# E77N.net
KiCad netlist of a schematic drawn in Altium Designer
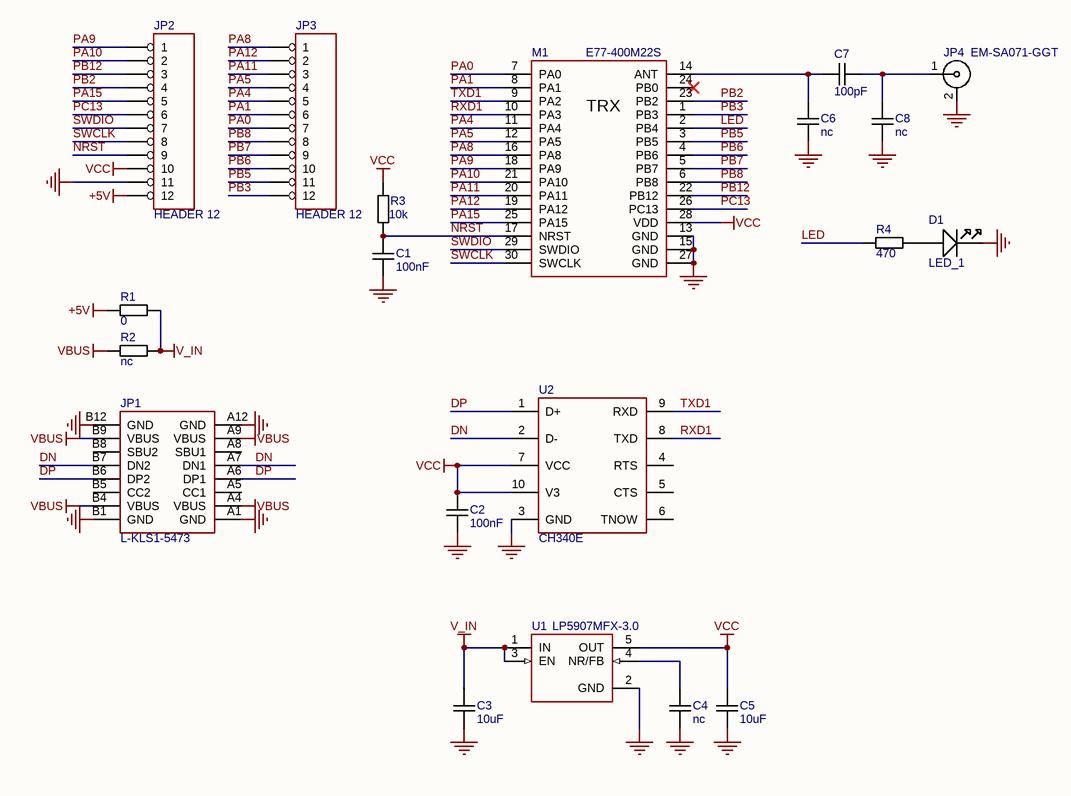
[diagram p0: E77N.SchDoc]

(export (version "E")
  (design (tool "Eeschema 10.0.6"))
  (components
    (comp (ref "C1")
      (value "100nF")
      (footprint "C-0603")
      (fields (field (name "VOLTAGE") "50V"))
      (libsource (lib "Passive") (part "CAPN"))
    )
    (comp (ref "C2")
      (value "100nF")
      (footprint "C-0603")
      (fields (field (name "VOLTAGE") "50V"))
      (libsource (lib "Passive") (part "CAPN"))
    )
    (comp (ref "C3")
      (value "10uF")
      (footprint "C-0805")
      (fields (field (name "VOLTAGE") "50V"))
      (libsource (lib "Passive") (part "CAPN"))
    )
    (comp (ref "C4")
      (value "nc")
      (footprint "C-0603")
      (fields (field (name "VOLTAGE") "50V"))
      (libsource (lib "Passive") (part "CAPN"))
    )
    (comp (ref "C5")
      (value "10uF")
      (footprint "C-0805")
      (fields (field (name "VOLTAGE") "50V"))
      (libsource (lib "Passive") (part "CAPN"))
    )
    (comp (ref "C6")
      (value "nc")
      (footprint "C-0603")
      (fields (field (name "VOLTAGE") "50V"))
      (libsource (lib "Passive") (part "CAPN"))
    )
    (comp (ref "C7")
      (value "100pF")
      (footprint "C-0603")
      (fields (field (name "VOLTAGE") "50V"))
      (libsource (lib "Passive") (part "CAPN"))
    )
    (comp (ref "C8")
      (value "nc")
      (footprint "C-0603")
      (fields (field (name "VOLTAGE") "50V"))
      (libsource (lib "Passive") (part "CAPN"))
    )
    (comp (ref "D1") (value "LED_1") (footprint "LED_0805") (libsource (lib "Diodes") (part "LED_1")))
    (comp (ref "JP1")
      (value "L-KLS1-5473")
      (footprint "USB_C_SMD_SLOT")
      (libsource (lib "Connectors") (part "L-KLS1-5473"))
    )
    (comp (ref "JP2")
      (value "HEADER 12")
      (footprint "PLS1-12")
      (libsource (lib "Connectors") (part "HEADER 12"))
    )
    (comp (ref "JP3")
      (value "HEADER 12")
      (footprint "PLS1-12")
      (libsource (lib "Connectors") (part "HEADER 12"))
    )
    (comp (ref "JP4")
      (value "EM-SA071-GGT")
      (footprint "SMA_F_EDGE")
      (description "SMA Female R/A PCB Mount")
      (libsource (lib "Connectors") (part "SMA"))
    )
    (comp (ref "M1")
      (value "E77-400M22S")
      (footprint "E77XX-M22")
      (libsource (lib "RFmodules") (part "E77-400M22S"))
    )
    (comp (ref "R1") (value "0") (footprint "R-0603") (libsource (lib "") (part "RES_1")))
    (comp (ref "R2") (value "nc") (footprint "R-0603") (libsource (lib "") (part "RES_1")))
    (comp (ref "R3") (value "10k") (footprint "R-0603") (libsource (lib "Passive") (part "RES")))
    (comp (ref "R4") (value "470") (footprint "R-0603") (libsource (lib "") (part "RES_2")))
    (comp (ref "U1")
      (value "LP5907MFX-3.0")
      (footprint "SOT-23-5")
      (description "250mA Low-Dropout Regulator")
      (libsource (lib "ICs") (part "LP5907"))
    )
    (comp (ref "U2") (value "CH340E") (footprint "MSOP-10") (libsource (lib "ICs") (part "CH340E")))
  )
  (nets
    (net (code "1") (name "+5V") (class "Default")
      (node (ref "JP2") (pin "12") (pinfunction "12_12") (pintype "passive"))
      (node (ref "R1") (pin "1") (pinfunction "1_1") (pintype "passive"))
    )
    (net (code "2") (name "/DN") (class "Default")
      (node (ref "JP1") (pin "A7") (pinfunction "DN1_A7") (pintype "passive"))
      (node (ref "JP1") (pin "B7") (pinfunction "DN2_B7") (pintype "passive"))
      (node (ref "U2") (pin "2") (pinfunction "D-_2") (pintype "passive"))
    )
    (net (code "3") (name "/DP") (class "Default")
      (node (ref "JP1") (pin "A6") (pinfunction "DP1_A6") (pintype "passive"))
      (node (ref "JP1") (pin "B6") (pinfunction "DP2_B6") (pintype "passive"))
      (node (ref "U2") (pin "1") (pinfunction "D+_1") (pintype "passive"))
    )
    (net (code "4") (name "/LED") (class "Default")
      (node (ref "M1") (pin "2") (pinfunction "PB4_2") (pintype "passive"))
      (node (ref "R4") (pin "2") (pinfunction "2_2") (pintype "passive"))
    )
    (net (code "5") (name "/NRST") (class "Default")
      (node (ref "C1") (pin "2") (pinfunction "2_2") (pintype "passive"))
      (node (ref "JP2") (pin "9") (pinfunction "9_9") (pintype "passive"))
      (node (ref "M1") (pin "17") (pinfunction "NRST_17") (pintype "passive"))
      (node (ref "R3") (pin "1") (pinfunction "1_1") (pintype "passive"))
    )
    (net (code "6") (name "/PA0") (class "Default")
      (node (ref "JP3") (pin "7") (pinfunction "7_7") (pintype "passive"))
      (node (ref "M1") (pin "7") (pinfunction "PA0_7") (pintype "passive"))
    )
    (net (code "7") (name "/PA1") (class "Default")
      (node (ref "JP3") (pin "6") (pinfunction "6_6") (pintype "passive"))
      (node (ref "M1") (pin "8") (pinfunction "PA1_8") (pintype "passive"))
    )
    (net (code "8") (name "/PA4") (class "Default")
      (node (ref "JP3") (pin "5") (pinfunction "5_5") (pintype "passive"))
      (node (ref "M1") (pin "11") (pinfunction "PA4_11") (pintype "passive"))
    )
    (net (code "9") (name "/PA5") (class "Default")
      (node (ref "JP3") (pin "4") (pinfunction "4_4") (pintype "passive"))
      (node (ref "M1") (pin "12") (pinfunction "PA5_12") (pintype "passive"))
    )
    (net (code "10") (name "/PA8") (class "Default")
      (node (ref "JP3") (pin "1") (pinfunction "1_1") (pintype "passive"))
      (node (ref "M1") (pin "16") (pinfunction "PA8_16") (pintype "passive"))
    )
    (net (code "11") (name "/PA9") (class "Default")
      (node (ref "JP2") (pin "1") (pinfunction "1_1") (pintype "passive"))
      (node (ref "M1") (pin "18") (pinfunction "PA9_18") (pintype "passive"))
    )
    (net (code "12") (name "/PA10") (class "Default")
      (node (ref "JP2") (pin "2") (pinfunction "2_2") (pintype "passive"))
      (node (ref "M1") (pin "21") (pinfunction "PA10_21") (pintype "passive"))
    )
    (net (code "13") (name "/PA11") (class "Default")
      (node (ref "JP3") (pin "3") (pinfunction "3_3") (pintype "passive"))
      (node (ref "M1") (pin "20") (pinfunction "PA11_20") (pintype "passive"))
    )
    (net (code "14") (name "/PA12") (class "Default")
      (node (ref "JP3") (pin "2") (pinfunction "2_2") (pintype "passive"))
      (node (ref "M1") (pin "19") (pinfunction "PA12_19") (pintype "passive"))
    )
    (net (code "15") (name "/PA15") (class "Default")
      (node (ref "JP2") (pin "5") (pinfunction "5_5") (pintype "passive"))
      (node (ref "M1") (pin "25") (pinfunction "PA15_25") (pintype "passive"))
    )
    (net (code "16") (name "/PB2") (class "Default")
      (node (ref "JP2") (pin "4") (pinfunction "4_4") (pintype "passive"))
      (node (ref "M1") (pin "23") (pinfunction "PB2_23") (pintype "passive"))
    )
    (net (code "17") (name "/PB3") (class "Default")
      (node (ref "JP3") (pin "12") (pinfunction "12_12") (pintype "passive"))
      (node (ref "M1") (pin "1") (pinfunction "PB3_1") (pintype "passive"))
    )
    (net (code "18") (name "/PB5") (class "Default")
      (node (ref "JP3") (pin "11") (pinfunction "11_11") (pintype "passive"))
      (node (ref "M1") (pin "3") (pinfunction "PB5_3") (pintype "passive"))
    )
    (net (code "19") (name "/PB6") (class "Default")
      (node (ref "JP3") (pin "10") (pinfunction "10_10") (pintype "passive"))
      (node (ref "M1") (pin "4") (pinfunction "PB6_4") (pintype "passive"))
    )
    (net (code "20") (name "/PB7") (class "Default")
      (node (ref "JP3") (pin "9") (pinfunction "9_9") (pintype "passive"))
      (node (ref "M1") (pin "5") (pinfunction "PB7_5") (pintype "passive"))
    )
    (net (code "21") (name "/PB8") (class "Default")
      (node (ref "JP3") (pin "8") (pinfunction "8_8") (pintype "passive"))
      (node (ref "M1") (pin "6") (pinfunction "PB8_6") (pintype "passive"))
    )
    (net (code "22") (name "/PB12") (class "Default")
      (node (ref "JP2") (pin "3") (pinfunction "3_3") (pintype "passive"))
      (node (ref "M1") (pin "22") (pinfunction "PB12_22") (pintype "passive"))
    )
    (net (code "23") (name "/PC13") (class "Default")
      (node (ref "JP2") (pin "6") (pinfunction "6_6") (pintype "passive"))
      (node (ref "M1") (pin "26") (pinfunction "PC13_26") (pintype "passive"))
    )
    (net (code "24") (name "/RXD1") (class "Default")
      (node (ref "M1") (pin "10") (pinfunction "PA3_10") (pintype "passive"))
      (node (ref "U2") (pin "8") (pinfunction "TXD_8") (pintype "passive"))
    )
    (net (code "25") (name "/SWCLK") (class "Default")
      (node (ref "JP2") (pin "8") (pinfunction "8_8") (pintype "passive"))
      (node (ref "M1") (pin "30") (pinfunction "SWCLK_30") (pintype "passive"))
    )
    (net (code "26") (name "/SWDIO") (class "Default")
      (node (ref "JP2") (pin "7") (pinfunction "7_7") (pintype "passive"))
      (node (ref "M1") (pin "29") (pinfunction "SWDIO_29") (pintype "passive"))
    )
    (net (code "27") (name "/TXD1") (class "Default")
      (node (ref "M1") (pin "9") (pinfunction "PA2_9") (pintype "passive"))
      (node (ref "U2") (pin "9") (pinfunction "RXD_9") (pintype "passive"))
    )
    (net (code "28") (name "GND") (class "Default")
      (node (ref "C1") (pin "1") (pinfunction "1_1") (pintype "passive"))
      (node (ref "C2") (pin "1") (pinfunction "1_1") (pintype "passive"))
      (node (ref "C3") (pin "2") (pinfunction "2_2") (pintype "passive"))
      (node (ref "C4") (pin "2") (pinfunction "2_2") (pintype "passive"))
      (node (ref "C5") (pin "2") (pinfunction "2_2") (pintype "passive"))
      (node (ref "C6") (pin "1") (pinfunction "1_1") (pintype "passive"))
      (node (ref "C8") (pin "1") (pinfunction "1_1") (pintype "passive"))
      (node (ref "D1") (pin "K") (pinfunction "CATHODE_K") (pintype "passive"))
      (node (ref "JP1") (pin "A1") (pinfunction "GND_A1") (pintype "passive"))
      (node (ref "JP1") (pin "A12") (pinfunction "GND_A12") (pintype "passive"))
      (node (ref "JP1") (pin "B1") (pinfunction "GND_B1") (pintype "passive"))
      (node (ref "JP1") (pin "B12") (pinfunction "GND_B12") (pintype "passive"))
      (node (ref "JP2") (pin "11") (pinfunction "11_11") (pintype "passive"))
      (node (ref "JP4") (pin "2") (pinfunction "2_2") (pintype "passive"))
      (node (ref "M1") (pin "13") (pinfunction "GND_13") (pintype "passive"))
      (node (ref "M1") (pin "15") (pinfunction "GND_15") (pintype "passive"))
      (node (ref "M1") (pin "27") (pinfunction "GND_27") (pintype "passive"))
      (node (ref "U1") (pin "2") (pinfunction "GND_2") (pintype "power_in"))
      (node (ref "U2") (pin "3") (pinfunction "GND_3") (pintype "passive"))
    )
    (net (code "29") (name "Net-(C7-Pad2)") (class "Default")
      (node (ref "C7") (pin "2") (pinfunction "2_2") (pintype "passive"))
      (node (ref "C8") (pin "2") (pinfunction "2_2") (pintype "passive"))
      (node (ref "JP4") (pin "1") (pinfunction "1_1") (pintype "passive"))
    )
    (net (code "30") (name "Net-(D1-ANODE)") (class "Default")
      (node (ref "D1") (pin "A") (pinfunction "ANODE_A") (pintype "passive"))
      (node (ref "R4") (pin "1") (pinfunction "1_1") (pintype "passive"))
    )
    (net (code "31") (name "Net-(M1-ANT)") (class "Default")
      (node (ref "C6") (pin "2") (pinfunction "2_2") (pintype "passive"))
      (node (ref "C7") (pin "1") (pinfunction "1_1") (pintype "passive"))
      (node (ref "M1") (pin "14") (pinfunction "ANT_14") (pintype "passive"))
    )
    (net (code "32") (name "Net-(U1-NR{slash}FB)") (class "Default")
      (node (ref "C4") (pin "1") (pinfunction "1_1") (pintype "passive"))
      (node (ref "U1") (pin "4") (pinfunction "NR/FB_4") (pintype "input"))
    )
    (net (code "33") (name "VBUS") (class "Default")
      (node (ref "JP1") (pin "A4") (pinfunction "VBUS_A4") (pintype "passive"))
      (node (ref "JP1") (pin "A9") (pinfunction "VBUS_A9") (pintype "passive"))
      (node (ref "JP1") (pin "B4") (pinfunction "VBUS_B4") (pintype "passive"))
      (node (ref "JP1") (pin "B9") (pinfunction "VBUS_B9") (pintype "passive"))
      (node (ref "R2") (pin "1") (pinfunction "1_1") (pintype "passive"))
    )
    (net (code "34") (name "VCC") (class "Default")
      (node (ref "C2") (pin "2") (pinfunction "2_2") (pintype "passive"))
      (node (ref "C5") (pin "1") (pinfunction "1_1") (pintype "passive"))
      (node (ref "JP2") (pin "10") (pinfunction "10_10") (pintype "passive"))
      (node (ref "M1") (pin "28") (pinfunction "VDD_28") (pintype "passive"))
      (node (ref "R3") (pin "2") (pinfunction "2_2") (pintype "passive"))
      (node (ref "U1") (pin "5") (pinfunction "OUT_5") (pintype "power_in"))
      (node (ref "U2") (pin "10") (pinfunction "V3_10") (pintype "passive"))
      (node (ref "U2") (pin "7") (pinfunction "VCC_7") (pintype "passive"))
    )
    (net (code "35") (name "VSS") (class "Default")
      (node (ref "JP1") (pin "17") (pinfunction "VSS_17") (pintype "power_in"))
    )
    (net (code "36") (name "V_IN") (class "Default")
      (node (ref "C3") (pin "1") (pinfunction "1_1") (pintype "passive"))
      (node (ref "R1") (pin "2") (pinfunction "2_2") (pintype "passive"))
      (node (ref "R2") (pin "2") (pinfunction "2_2") (pintype "passive"))
      (node (ref "U1") (pin "1") (pinfunction "IN_1") (pintype "power_in"))
      (node (ref "U1") (pin "3") (pinfunction "EN_3") (pintype "input"))
    )
    (net (code "37") (name "unconnected-(JP1-CC1-PadA5)") (class "Default")
      (node (ref "JP1") (pin "A5") (pinfunction "CC1_A5") (pintype "passive"))
    )
    (net (code "38") (name "unconnected-(JP1-CC2-PadB5)") (class "Default")
      (node (ref "JP1") (pin "B5") (pinfunction "CC2_B5") (pintype "passive"))
    )
    (net (code "39") (name "unconnected-(JP1-SBU1-PadA8)") (class "Default")
      (node (ref "JP1") (pin "A8") (pinfunction "SBU1_A8") (pintype "passive"))
    )
    (net (code "40") (name "unconnected-(JP1-SBU2-PadB8)") (class "Default")
      (node (ref "JP1") (pin "B8") (pinfunction "SBU2_B8") (pintype "passive"))
    )
    (net (code "41") (name "unconnected-(M1-PB0-Pad24)") (class "Default")
      (node (ref "M1") (pin "24") (pinfunction "PB0_24") (pintype "passive+no_connect"))
    )
    (net (code "42") (name "unconnected-(U2-CTS-Pad5)") (class "Default")
      (node (ref "U2") (pin "5") (pinfunction "CTS_5") (pintype "passive"))
    )
    (net (code "43") (name "unconnected-(U2-RTS-Pad4)") (class "Default")
      (node (ref "U2") (pin "4") (pinfunction "RTS_4") (pintype "passive"))
    )
    (net (code "44") (name "unconnected-(U2-TNOW-Pad6)") (class "Default")
      (node (ref "U2") (pin "6") (pinfunction "TNOW_6") (pintype "passive"))
    )
  )
)
